# MCU.net
KiCad netlist of a schematic drawn in Altium Designer
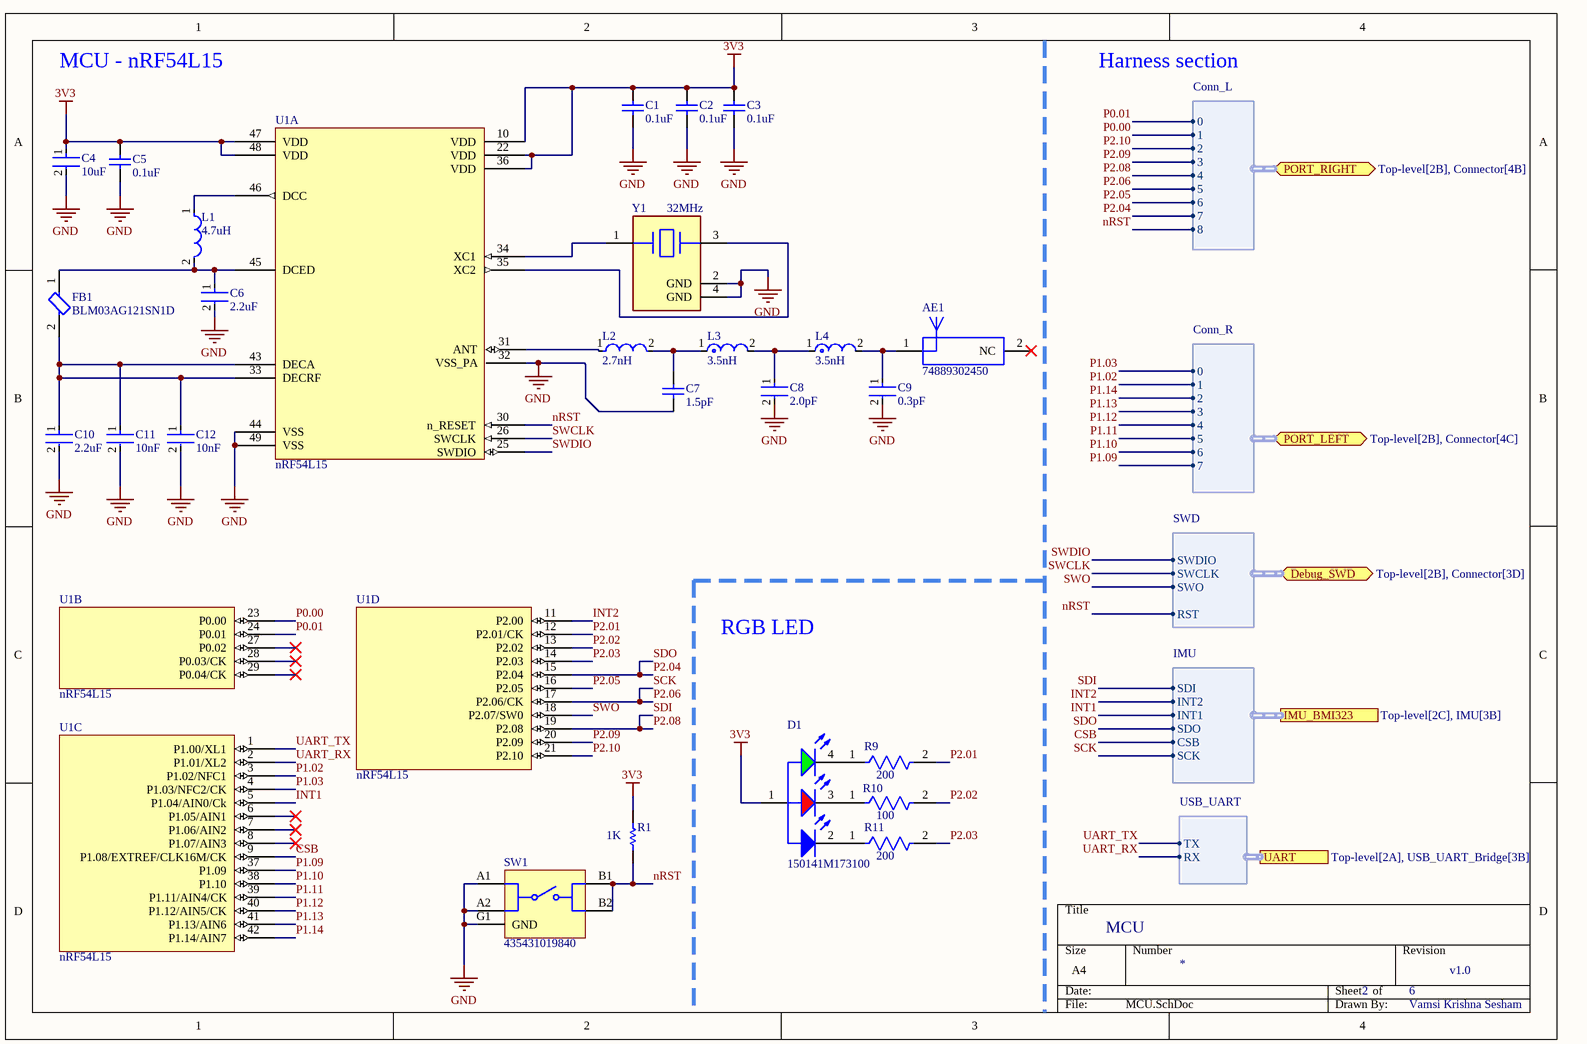
[diagram p0: MCU.SchDoc]

(export (version "E")
  (design (tool "Eeschema 10.0.6"))
  (components
    (comp (ref "AE1")
      (value "74889302450")
      (footprint "74889302450")
      (description "74889302450 Chip Antenna, 2.45Ghz, 3.2Mm X 1.6Mm X 1.2Mm Rohs Compliant: Yes")
      (libsource (lib "Altium Content Vault") (part "74889302450"))
    )
    (comp (ref "C1")
      (value "0.1uF")
      (footprint "CAPC0603X33X15ML03T05")
      (fields (field (name "MANUFACTURER") "Samsung") (field (name "PART NUMBER") "CL03A104KQ3NNNC"))
      (libsource (lib "Altium Content Vault") (part "CAP"))
    )
    (comp (ref "C2")
      (value "0.1uF")
      (footprint "CAPC0603X33X15ML03T05")
      (fields (field (name "MANUFACTURER") "Samsung") (field (name "PART NUMBER") "CL03A104KQ3NNNC"))
      (libsource (lib "Altium Content Vault") (part "CAP"))
    )
    (comp (ref "C3")
      (value "0.1uF")
      (footprint "CAPC0603X33X15ML03T05")
      (fields (field (name "MANUFACTURER") "Samsung") (field (name "PART NUMBER") "CL03A104KQ3NNNC"))
      (libsource (lib "Altium Content Vault") (part "CAP"))
    )
    (comp (ref "C4")
      (value "10uF")
      (footprint "FP-CL07-IPC_C")
      (description "Cap Ceramic 10uF 10V X5R ±20% SMD 0402 +85°C Paper T/R")
      (fields (field (name "TOLERANCE") "20%"))
      (libsource (lib "Altium Content Vault") (part "b4654b650e69147ec39a6b967a45e02"))
    )
    (comp (ref "C5")
      (value "0.1uF")
      (footprint "CAPC0603X33X15ML03T05")
      (fields (field (name "MANUFACTURER") "Samsung") (field (name "PART NUMBER") "CL03A104KQ3NNNC"))
      (libsource (lib "Altium Content Vault") (part "CAP"))
    )
    (comp (ref "C6")
      (value "2.2uF")
      (footprint "FP-CL03-IPC_B")
      (description "Cap Ceramic 2.2uF 10V X5R ±20% Pad SMD 0201 +85°C T/R")
      (fields (field (name "TOLERANCE") "20%"))
      (libsource (lib "Altium Content Vault") (part "b4654b650e69147ec39a6b967a45e02"))
    )
    (comp (ref "C7")
      (value "1.5pF")
      (footprint "CAPC0603X33X15NL03T05")
      (fields
        (field (name "PART NUMBER") "02013A1R5CAT2A")
        (field (name "MANUFACTURER") "AVX Interconnect / Elco")
      )
      (libsource (lib "Altium Content Vault") (part "CAP"))
    )
    (comp (ref "C8")
      (value "2.0pF")
      (footprint "FP-GRM033-0_03-MFG")
      (description "Chip Multilayer Ceramic Capacitors for General Purpose, 0201, 2.0pF, C0G, 30ppm/°C, 0.25pF, 25V")
      (libsource (lib "Altium Content Vault") (part "b4654b650e69147ec39a6b967a45e02"))
    )
    (comp (ref "C9")
      (value "0.3pF")
      (footprint "FP-GJM033-0_03-IPC_A")
      (description "Ceramic Capacitor 0.3pF ±0.05pF 25V C0G 0201 (0603 Metric)")
      (libsource (lib "Altium Content Vault") (part "b4654b650e69147ec39a6b967a45e02"))
    )
    (comp (ref "C10")
      (value "2.2uF")
      (footprint "FP-CL03-IPC_B")
      (description "Cap Ceramic 2.2uF 10V X5R ±20% Pad SMD 0201 +85°C T/R")
      (fields (field (name "TOLERANCE") "20%"))
      (libsource (lib "Altium Content Vault") (part "b4654b650e69147ec39a6b967a45e02"))
    )
    (comp (ref "C11")
      (value "10nF")
      (footprint "FP-GRM033-0_03-IPC_B")
      (description "Chip Multilayer Ceramic Capacitors for General Purpose, 0201, 10000pF, X7R, 15%, 10%, 10V")
      (fields (field (name "VOLTAGE") "10V") (field (name "TOLERANCE") "10%"))
      (libsource (lib "Altium Content Vault") (part "b4654b650e69147ec39a6b967a45e02"))
    )
    (comp (ref "C12")
      (value "10nF")
      (footprint "FP-GRM033-0_03-IPC_B")
      (description "Chip Multilayer Ceramic Capacitors for General Purpose, 0201, 10000pF, X7R, 15%, 10%, 10V")
      (fields (field (name "VOLTAGE") "10V") (field (name "TOLERANCE") "10%"))
      (libsource (lib "Altium Content Vault") (part "b4654b650e69147ec39a6b967a45e02"))
    )
    (comp (ref "D1")
      (value "150141M173100")
      (footprint "WL-SFTW_3528_150141M173100")
      (libsource (lib "Altium Content Vault") (part "WL-SFTW_150141M173100"))
    )
    (comp (ref "FB1")
      (value "BLM03AG121SN1D")
      (footprint "FP-BLM03-0_03-d0_3-IPC_A")
      (description "Ferrite Bead, 0201, 120Ω @ 100MHz, 25%, 0.5Ω, 200mA")
      (fields (field (name "TOLERANCE") "25%"))
      (libsource (lib "Altium Content Vault") (part "5f30dd21d616792df468990f7003faa"))
    )
    (comp (ref "L1")
      (value "4.7uH")
      (footprint "FP-MLZ1608-IPC_A")
      (description "Shielded Multilayer Inductor 4.7uH ±20% 350mA 650mΩ SMD 0603")
      (fields (field (name "TOLERANCE") "20%"))
      (libsource (lib "Altium Content Vault") (part "725321dda6339637d4d059423bc1c3c"))
    )
    (comp (ref "L2")
      (value "2.7nH")
      (footprint "FP-LQP03HQ_02-MFG")
      (description "Film type RF Inductor 2.7nH ±0.1nH 600mA 0.12Ω 0201 (0603)")
      (libsource (lib "Altium Content Vault") (part "725321dda6339637d4d059423bc1c3c"))
    )
    (comp (ref "L3")
      (value "3.5nH")
      (footprint "FP-LQP03TG_02-IPC_C")
      (description "Film type RF Inductor 3.5nH ±0.1nH 450mA 0.25Ω 0201 (0603)")
      (libsource (lib "Altium Content Vault") (part "4cc4b267dca4c8e51f7102f422741d8"))
    )
    (comp (ref "L4")
      (value "3.5nH")
      (footprint "FP-LQP03TG_02-IPC_C")
      (description "Film type RF Inductor 3.5nH ±0.1nH 450mA 0.25Ω 0201 (0603)")
      (libsource (lib "Altium Content Vault") (part "4cc4b267dca4c8e51f7102f422741d8"))
    )
    (comp (ref "R1")
      (value "1K")
      (footprint "RESC0603X28X15ML05T05")
      (fields (field (name "MANUFACTURER") "Vishay Dale") (field (name "PART NUMBER") "CRCW02011K00FNED"))
      (libsource (lib "Altium Content Vault") (part "RES"))
    )
    (comp (ref "R9")
      (value "200")
      (footprint "FP-ERJ1GN-MFG")
      (description "RES SMD 200 OHM 1% 1/20W 0201")
      (fields (field (name "TOLERANCE") "1%") (field (name "MANUFACTURER PART NUMBER") "ERJ-1GNF2000C"))
      (libsource (lib "Altium Content Vault") (part "1029c3af85768c4190bb7ad29bc67b5"))
    )
    (comp (ref "R10")
      (value "100")
      (footprint "FP-ERJ1GN-MFG")
      (description "RES SMD 200 OHM 1% 1/20W 0201")
      (fields (field (name "TOLERANCE") "1%") (field (name "MANUFACTURER PART NUMBER") "ERJ-1GNF2000C"))
      (libsource (lib "Altium Content Vault") (part "1029c3af85768c4190bb7ad29bc67b5"))
    )
    (comp (ref "R11")
      (value "200")
      (footprint "FP-ERJ1GN-MFG")
      (description "RES SMD 200 OHM 1% 1/20W 0201")
      (fields (field (name "TOLERANCE") "1%") (field (name "MANUFACTURER PART NUMBER") "ERJ-1GNF2000C"))
      (libsource (lib "Altium Content Vault") (part "1029c3af85768c4190bb7ad29bc67b5"))
    )
    (comp (ref "SW1")
      (value "435431019840")
      (footprint "435431019840")
      (description "Tactile Switch, 0.05A, 32VDC, SMD, 400GF Rohs Compliant: Yes")
      (libsource (lib "Altium Content Vault") (part "SPST-NO_4P_1GND"))
    )
    (comp (ref "U1")
      (value "nRF54L15")
      (footprint "nRF54L15_QFN8_6X6")
      (description "Ultra-low-power wireless SoC")
      (libsource (lib "MyCustomLib") (part "nRF54L15_QFN8_6X6"))
    )
    (comp (ref "Y1")
      (value "32MHz")
      (footprint "FP-ABM8G-MFG")
      (description "Crystal 32MHz ±30ppm (Tol) ±30ppm (Stability) 10pF FUND 50Ω 4-Pin SMD T/R")
      (fields (field (name "TOLERANCE") "30ppm"))
      (libsource (lib "Altium Content Vault") (part "48e526d86b7f2615d98721063c72f49"))
    )
  )
  (nets
    (net (code "6") (name "/CSB") (class "Default")
      (node (ref "U1") (pin "9") (pinfunction "P1.08/EXTREF/CLK16M/CK_9") (pintype "bidirectional"))
    )
    (net (code "7") (name "/INT1") (class "Default")
      (node (ref "U1") (pin "5") (pinfunction "P1.04/AIN0/Ck_5") (pintype "bidirectional"))
    )
    (net (code "8") (name "/INT2") (class "Default")
      (node (ref "U1") (pin "11") (pinfunction "P2.00_11") (pintype "bidirectional"))
    )
    (net (code "9") (name "/P0.00") (class "Default")
      (node (ref "U1") (pin "23") (pinfunction "P0.00_23") (pintype "bidirectional"))
    )
    (net (code "10") (name "/P0.01") (class "Default")
      (node (ref "U1") (pin "24") (pinfunction "P0.01_24") (pintype "bidirectional"))
    )
    (net (code "11") (name "/P1.02") (class "Default")
      (node (ref "U1") (pin "3") (pinfunction "P1.02/NFC1_3") (pintype "bidirectional"))
    )
    (net (code "12") (name "/P1.03") (class "Default")
      (node (ref "U1") (pin "4") (pinfunction "P1.03/NFC2/CK_4") (pintype "bidirectional"))
    )
    (net (code "13") (name "/P1.09") (class "Default")
      (node (ref "U1") (pin "37") (pinfunction "P1.09_37") (pintype "bidirectional"))
    )
    (net (code "14") (name "/P1.10") (class "Default")
      (node (ref "U1") (pin "38") (pinfunction "P1.10_38") (pintype "bidirectional"))
    )
    (net (code "15") (name "/P1.11") (class "Default")
      (node (ref "U1") (pin "39") (pinfunction "P1.11/AIN4/CK_39") (pintype "bidirectional"))
    )
    (net (code "16") (name "/P1.12") (class "Default")
      (node (ref "U1") (pin "40") (pinfunction "P1.12/AIN5/CK_40") (pintype "bidirectional"))
    )
    (net (code "17") (name "/P1.13") (class "Default")
      (node (ref "U1") (pin "41") (pinfunction "P1.13/AIN6_41") (pintype "bidirectional"))
    )
    (net (code "18") (name "/P1.14") (class "Default")
      (node (ref "U1") (pin "42") (pinfunction "P1.14/AIN7_42") (pintype "bidirectional"))
    )
    (net (code "19") (name "/P2.01") (class "Default")
      (node (ref "R9") (pin "2") (pinfunction "2_2") (pintype "passive"))
      (node (ref "U1") (pin "12") (pinfunction "P2.01/CK_12") (pintype "bidirectional"))
    )
    (net (code "20") (name "/P2.02") (class "Default")
      (node (ref "R10") (pin "2") (pinfunction "2_2") (pintype "passive"))
      (node (ref "U1") (pin "13") (pinfunction "P2.02_13") (pintype "bidirectional"))
    )
    (net (code "21") (name "/P2.03") (class "Default")
      (node (ref "R11") (pin "2") (pinfunction "2_2") (pintype "passive"))
      (node (ref "U1") (pin "14") (pinfunction "P2.03_14") (pintype "bidirectional"))
    )
    (net (code "22") (name "/P2.04") (class "Default")
      (node (ref "U1") (pin "15") (pinfunction "P2.04_15") (pintype "bidirectional"))
    )
    (net (code "23") (name "/P2.05") (class "Default")
      (node (ref "U1") (pin "16") (pinfunction "P2.05_16") (pintype "bidirectional"))
    )
    (net (code "24") (name "/P2.06") (class "Default")
      (node (ref "U1") (pin "17") (pinfunction "P2.06/CK_17") (pintype "bidirectional"))
    )
    (net (code "25") (name "/P2.08") (class "Default")
      (node (ref "U1") (pin "19") (pinfunction "P2.08_19") (pintype "bidirectional"))
    )
    (net (code "26") (name "/P2.09") (class "Default")
      (node (ref "U1") (pin "20") (pinfunction "P2.09_20") (pintype "bidirectional"))
    )
    (net (code "27") (name "/P2.10") (class "Default")
      (node (ref "U1") (pin "21") (pinfunction "P2.10_21") (pintype "bidirectional"))
    )
    (net (code "28") (name "/SWCLK") (class "Default")
      (node (ref "U1") (pin "26") (pinfunction "SWCLK_26") (pintype "input"))
    )
    (net (code "29") (name "/SWDIO") (class "Default")
      (node (ref "U1") (pin "25") (pinfunction "SWDIO_25") (pintype "bidirectional"))
    )
    (net (code "30") (name "/SWO") (class "Default")
      (node (ref "U1") (pin "18") (pinfunction "P2.07/SW0_18") (pintype "bidirectional"))
    )
    (net (code "31") (name "/UART_RX") (class "Default")
      (node (ref "U1") (pin "2") (pinfunction "P1.01/XL2_2") (pintype "bidirectional"))
    )
    (net (code "32") (name "/UART_TX") (class "Default")
      (node (ref "U1") (pin "1") (pinfunction "P1.00/XL1_1") (pintype "bidirectional"))
    )
    (net (code "33") (name "/nRST") (class "Default")
      (node (ref "R1") (pin "1") (pinfunction "1_1") (pintype "passive"))
      (node (ref "SW1") (pin "B1") (pinfunction "B1_B1") (pintype "passive"))
      (node (ref "SW1") (pin "B2") (pinfunction "B2_B2") (pintype "passive"))
      (node (ref "U1") (pin "30") (pinfunction "n_RESET_30") (pintype "input"))
    )
    (net (code "39") (name "3V3") (class "Default")
      (node (ref "C1") (pin "2") (pinfunction "2_2") (pintype "passive"))
      (node (ref "C2") (pin "2") (pinfunction "2_2") (pintype "passive"))
      (node (ref "C3") (pin "2") (pinfunction "2_2") (pintype "passive"))
      (node (ref "C4") (pin "1") (pinfunction "1_1") (pintype "passive"))
      (node (ref "C5") (pin "2") (pinfunction "2_2") (pintype "passive"))
      (node (ref "D1") (pin "1") (pinfunction "A_1") (pintype "passive"))
      (node (ref "R1") (pin "2") (pinfunction "2_2") (pintype "passive"))
      (node (ref "U1") (pin "10") (pinfunction "VDD_10") (pintype "power_in"))
      (node (ref "U1") (pin "22") (pinfunction "VDD_22") (pintype "power_in"))
      (node (ref "U1") (pin "36") (pinfunction "VDD_36") (pintype "power_in"))
      (node (ref "U1") (pin "47") (pinfunction "VDD_47") (pintype "power_in"))
      (node (ref "U1") (pin "48") (pinfunction "VDD_48") (pintype "power_in"))
    )
    (net (code "40") (name "GND") (class "Default")
      (node (ref "C1") (pin "1") (pinfunction "1_1") (pintype "passive"))
      (node (ref "C10") (pin "2") (pinfunction "2_2") (pintype "passive"))
      (node (ref "C11") (pin "2") (pinfunction "2_2") (pintype "passive"))
      (node (ref "C12") (pin "2") (pinfunction "2_2") (pintype "passive"))
      (node (ref "C2") (pin "1") (pinfunction "1_1") (pintype "passive"))
      (node (ref "C3") (pin "1") (pinfunction "1_1") (pintype "passive"))
      (node (ref "C4") (pin "2") (pinfunction "2_2") (pintype "passive"))
      (node (ref "C5") (pin "1") (pinfunction "1_1") (pintype "passive"))
      (node (ref "C6") (pin "2") (pinfunction "2_2") (pintype "passive"))
      (node (ref "C7") (pin "1") (pinfunction "1_1") (pintype "passive"))
      (node (ref "C8") (pin "2") (pinfunction "2_2") (pintype "passive"))
      (node (ref "C9") (pin "2") (pinfunction "2_2") (pintype "passive"))
      (node (ref "SW1") (pin "A1") (pinfunction "A1_A1") (pintype "passive"))
      (node (ref "SW1") (pin "A2") (pinfunction "A2_A2") (pintype "passive"))
      (node (ref "SW1") (pin "G1") (pinfunction "GND_G1") (pintype "passive"))
      (node (ref "U1") (pin "32") (pinfunction "VSS_PA_32") (pintype "power_in"))
      (node (ref "U1") (pin "44") (pinfunction "VSS_44") (pintype "power_in"))
      (node (ref "U1") (pin "49") (pinfunction "VSS_49") (pintype "power_in"))
      (node (ref "Y1") (pin "2") (pinfunction "GND_2") (pintype "power_in"))
      (node (ref "Y1") (pin "4") (pinfunction "GND_4") (pintype "power_in"))
    )
    (net (code "41") (name "Net-(AE1-Feed)") (class "Default")
      (node (ref "AE1") (pin "1") (pinfunction "Feed_1") (pintype "passive"))
      (node (ref "C9") (pin "1") (pinfunction "1_1") (pintype "passive"))
      (node (ref "L4") (pin "2") (pinfunction "2_2") (pintype "passive"))
    )
    (net (code "42") (name "Net-(C7-Pad2)") (class "Default")
      (node (ref "C7") (pin "2") (pinfunction "2_2") (pintype "passive"))
      (node (ref "L2") (pin "2") (pinfunction "2_2") (pintype "passive"))
      (node (ref "L3") (pin "1") (pinfunction "1_1") (pintype "passive"))
    )
    (net (code "43") (name "Net-(C8-Pad1)") (class "Default")
      (node (ref "C8") (pin "1") (pinfunction "1_1") (pintype "passive"))
      (node (ref "L3") (pin "2") (pinfunction "2_2") (pintype "passive"))
      (node (ref "L4") (pin "1") (pinfunction "1_1") (pintype "passive"))
    )
    (net (code "44") (name "Net-(D1-K-Pad2)") (class "Default")
      (node (ref "D1") (pin "2") (pinfunction "K_2") (pintype "passive"))
      (node (ref "R11") (pin "1") (pinfunction "1_1") (pintype "passive"))
    )
    (net (code "45") (name "Net-(D1-K-Pad3)") (class "Default")
      (node (ref "D1") (pin "3") (pinfunction "K_3") (pintype "passive"))
      (node (ref "R10") (pin "1") (pinfunction "1_1") (pintype "passive"))
    )
    (net (code "46") (name "Net-(D1-K-Pad4)") (class "Default")
      (node (ref "D1") (pin "4") (pinfunction "K_4") (pintype "passive"))
      (node (ref "R9") (pin "1") (pinfunction "1_1") (pintype "passive"))
    )
    (net (code "47") (name "Net-(U1A-ANT)") (class "Default")
      (node (ref "L2") (pin "1") (pinfunction "1_1") (pintype "passive"))
      (node (ref "U1") (pin "31") (pinfunction "ANT_31") (pintype "bidirectional"))
    )
    (net (code "48") (name "Net-(U1A-DCC)") (class "Default")
      (node (ref "L1") (pin "1") (pinfunction "1_1") (pintype "passive"))
      (node (ref "U1") (pin "46") (pinfunction "DCC_46") (pintype "output"))
    )
    (net (code "49") (name "Net-(U1A-DCED)") (class "Default")
      (node (ref "C6") (pin "1") (pinfunction "1_1") (pintype "passive"))
      (node (ref "FB1") (pin "1") (pinfunction "1_1") (pintype "passive"))
      (node (ref "L1") (pin "2") (pinfunction "2_2") (pintype "passive"))
      (node (ref "U1") (pin "45") (pinfunction "DCED_45") (pintype "power_in"))
    )
    (net (code "50") (name "Net-(U1A-DECA)") (class "Default")
      (node (ref "C10") (pin "1") (pinfunction "1_1") (pintype "passive"))
      (node (ref "C11") (pin "1") (pinfunction "1_1") (pintype "passive"))
      (node (ref "C12") (pin "1") (pinfunction "1_1") (pintype "passive"))
      (node (ref "FB1") (pin "2") (pinfunction "2_2") (pintype "passive"))
      (node (ref "U1") (pin "33") (pinfunction "DECRF_33") (pintype "power_in"))
      (node (ref "U1") (pin "43") (pinfunction "DECA_43") (pintype "power_in"))
    )
    (net (code "51") (name "Net-(U1A-XC1)") (class "Default")
      (node (ref "U1") (pin "34") (pinfunction "XC1_34") (pintype "input"))
      (node (ref "Y1") (pin "1") (pinfunction "1_1") (pintype "passive"))
    )
    (net (code "52") (name "Net-(U1A-XC2)") (class "Default")
      (node (ref "U1") (pin "35") (pinfunction "XC2_35") (pintype "output"))
      (node (ref "Y1") (pin "3") (pinfunction "3_3") (pintype "passive"))
    )
    (net (code "53") (name "unconnected-(AE1-NC-Pad2)") (class "Default")
      (node (ref "AE1") (pin "2") (pinfunction "NC_2") (pintype "passive+no_connect"))
    )
    (net (code "54") (name "unconnected-(U1B-P0.02-Pad27)") (class "Default")
      (node (ref "U1") (pin "27") (pinfunction "P0.02_27") (pintype "bidirectional+no_connect"))
    )
    (net (code "55") (name "unconnected-(U1B-P0.03{slash}CK-Pad28)") (class "Default")
      (node (ref "U1") (pin "28") (pinfunction "P0.03/CK_28") (pintype "bidirectional+no_connect"))
    )
    (net (code "56") (name "unconnected-(U1B-P0.04{slash}CK-Pad29)") (class "Default")
      (node (ref "U1") (pin "29") (pinfunction "P0.04/CK_29") (pintype "bidirectional+no_connect"))
    )
    (net (code "57") (name "unconnected-(U1C-P1.05{slash}AIN1-Pad6)") (class "Default")
      (node (ref "U1") (pin "6") (pinfunction "P1.05/AIN1_6") (pintype "bidirectional+no_connect"))
    )
    (net (code "58") (name "unconnected-(U1C-P1.06{slash}AIN2-Pad7)") (class "Default")
      (node (ref "U1") (pin "7") (pinfunction "P1.06/AIN2_7") (pintype "bidirectional+no_connect"))
    )
    (net (code "59") (name "unconnected-(U1C-P1.07{slash}AIN3-Pad8)") (class "Default")
      (node (ref "U1") (pin "8") (pinfunction "P1.07/AIN3_8") (pintype "bidirectional+no_connect"))
    )
  )
)
